# tiny_sat_schematic.net
KiCad netlist of a schematic drawn in EAGLE
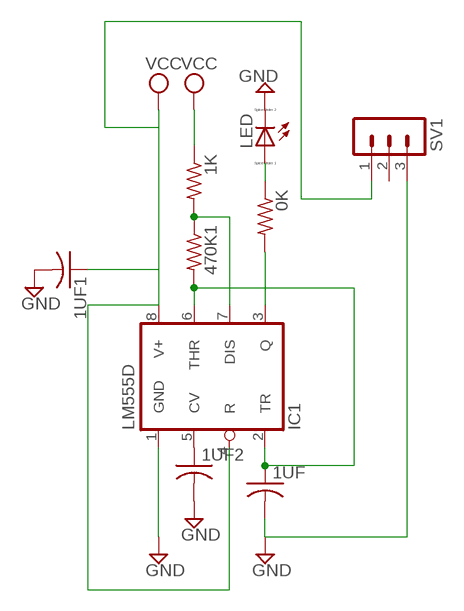
[diagram p0: schematic, sheet 1]

(export (version "E")
  (design (tool "Eeschema 10.0.6"))
  (components
    (comp (ref "0K")
      (value "R-US_R0805")
      (footprint "eagle-import:R0805")
      (libsource (lib "eagle-import") (part "R-US_R0805"))
    )
    (comp (ref "1K")
      (value "R-US_R0805")
      (footprint "eagle-import:R0805")
      (libsource (lib "eagle-import") (part "R-US_R0805"))
    )
    (comp (ref "1UF")
      (value "C-USC0805")
      (footprint "eagle-import:C0805")
      (libsource (lib "eagle-import") (part "C-USC0805"))
    )
    (comp (ref "1UF1")
      (value "C-USC0805")
      (footprint "eagle-import:C0805")
      (libsource (lib "eagle-import") (part "C-USC0805"))
    )
    (comp (ref "1UF2")
      (value "C-USC0805")
      (footprint "eagle-import:C0805")
      (libsource (lib "eagle-import") (part "C-USC0805"))
    )
    (comp (ref "470K1")
      (value "R-US_R0805")
      (footprint "eagle-import:R0805")
      (libsource (lib "eagle-import") (part "R-US_R0805"))
    )
    (comp (ref "IC1")
      (value "LM555D")
      (footprint "eagle-import:SO08")
      (libsource (lib "eagle-import") (part "555DLM"))
    )
    (comp (ref "LED")
      (value "LED_ELD260")
      (footprint "eagle-import:LED_LD260")
      (libsource (lib "eagle-import") (part "LED_ELD260"))
    )
    (comp (ref "SV1")
      (value "MA03-1")
      (footprint "eagle-import:MA03-1")
      (libsource (lib "eagle-import") (part "MA03-1"))
    )
  )
  (nets
    (net (code "1") (name "GND") (class "Default")
      (node (ref "1UF") (pin "2") (pinfunction "2_2") (pintype "passive"))
      (node (ref "1UF1") (pin "2") (pinfunction "2_2") (pintype "passive"))
      (node (ref "1UF2") (pin "2") (pinfunction "2_2") (pintype "passive"))
      (node (ref "IC1") (pin "1") (pinfunction "GND_1") (pintype "power_in"))
      (node (ref "LED") (pin "K") (pinfunction "C_K") (pintype "passive"))
      (node (ref "SV1") (pin "3") (pinfunction "3_3") (pintype "passive"))
    )
    (net (code "2") (name "Net-(0K-Pad1)") (class "Default")
      (node (ref "0K") (pin "1") (pinfunction "1_1") (pintype "passive"))
      (node (ref "LED") (pin "A") (pinfunction "A_A") (pintype "passive"))
    )
    (net (code "3") (name "Net-(IC1-CV)") (class "Default")
      (node (ref "1UF2") (pin "1") (pinfunction "1_1") (pintype "passive"))
      (node (ref "IC1") (pin "5") (pinfunction "CV_5") (pintype "input"))
    )
    (net (code "4") (name "Net-(IC1-DIS)") (class "Default")
      (node (ref "1K") (pin "2") (pinfunction "2_2") (pintype "passive"))
      (node (ref "470K1") (pin "1") (pinfunction "1_1") (pintype "passive"))
      (node (ref "IC1") (pin "7") (pinfunction "DIS_7") (pintype "input"))
    )
    (net (code "5") (name "Net-(IC1-Q)") (class "Default")
      (node (ref "0K") (pin "2") (pinfunction "2_2") (pintype "passive"))
      (node (ref "IC1") (pin "3") (pinfunction "Q_3") (pintype "output"))
    )
    (net (code "6") (name "Net-(IC1-THR)") (class "Default")
      (node (ref "1UF") (pin "1") (pinfunction "1_1") (pintype "passive"))
      (node (ref "470K1") (pin "2") (pinfunction "2_2") (pintype "passive"))
      (node (ref "IC1") (pin "2") (pinfunction "TR_2") (pintype "input"))
      (node (ref "IC1") (pin "6") (pinfunction "THR_6") (pintype "input"))
    )
    (net (code "7") (name "VCC") (class "Default")
      (node (ref "1K") (pin "1") (pinfunction "1_1") (pintype "passive"))
      (node (ref "1UF1") (pin "1") (pinfunction "1_1") (pintype "passive"))
      (node (ref "IC1") (pin "4") (pinfunction "R_4") (pintype "input"))
      (node (ref "IC1") (pin "8") (pinfunction "V+_8") (pintype "power_in"))
      (node (ref "SV1") (pin "1") (pinfunction "1_1") (pintype "passive"))
    )
    (net (code "8") (name "unconnected-(SV1-Pad2)") (class "Default")
      (node (ref "SV1") (pin "2") (pinfunction "2_2") (pintype "passive"))
    )
  )
)
